# Schematics_PranavHackCard.net
KiCad netlist of a schematic drawn in EasyEDA
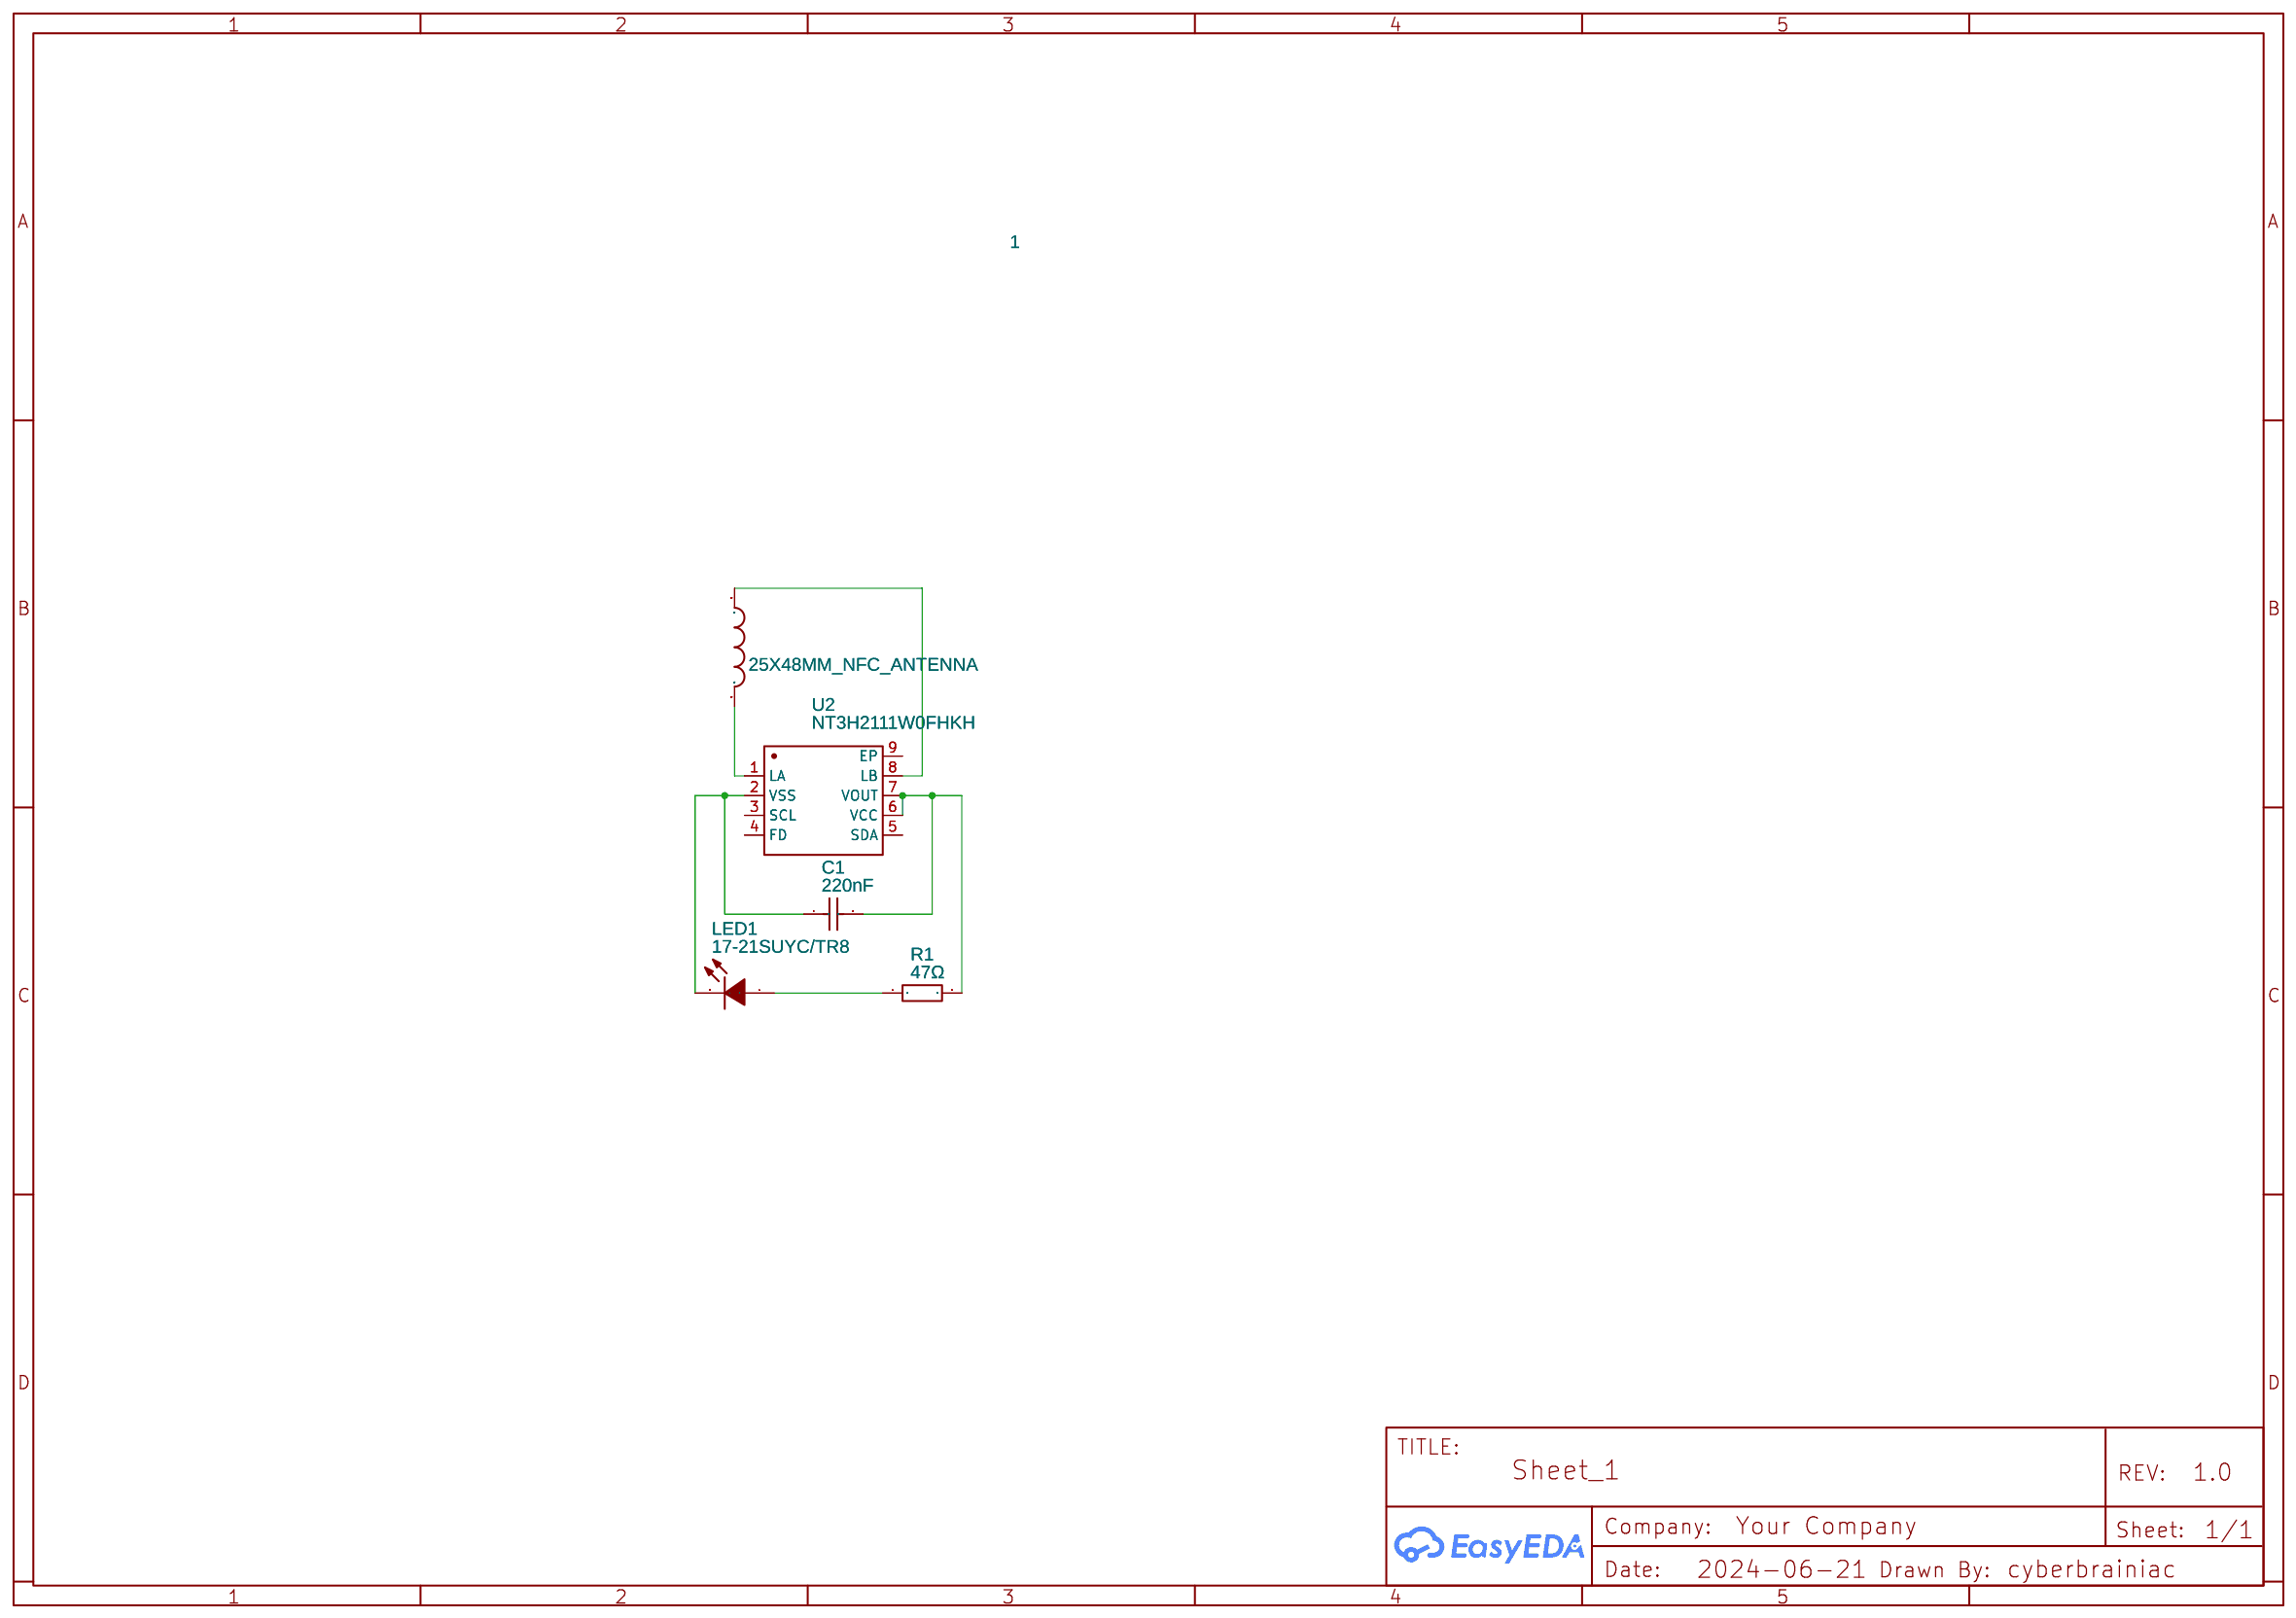
[diagram p0: schematic sheet]

(export (version "E")
  (design (tool "Eeschema 10.0.6"))
  (components
    (comp (ref "1") (value "25X48MM_NFC_ANTENNA") (libsource (lib "") (part "25X48MM_NFC_ANTENNA")))
    (comp (ref "C1")
      (value "220nF")
      (fields
        (field (name "Manufacturer Part") "CL10B224KA8NNNC")
        (field (name "Manufacturer") "SAMSUNG(三星)")
      )
      (libsource (lib "") (part "CL10B224KA8NNNC"))
    )
    (comp (ref "LED1")
      (value "17-21SUYC/TR8")
      (fields (field (name "Manufacturer Part") "KT-0805黄灯") (field (name "Manufacturer") "KENTO"))
      (libsource (lib "") (part "17-21SUYC/TR8"))
    )
    (comp (ref "R1")
      (value "47Ω")
      (fields
        (field (name "Manufacturer Part") "0603WAF470JT5E")
        (field (name "Manufacturer") "UNI-ROYAL(厚声)")
      )
      (libsource (lib "") (part "0603WAF470JT5E"))
    )
    (comp (ref "U2")
      (value "NT3H2111W0FHKH")
      (fields (field (name "Manufacturer") "NXP(恩智浦)"))
      (libsource (lib "") (part "NT3H2111W0FHKH"))
    )
  )
  (nets
    (net (code "1") (name "Net-(LED1-+)") (class "Default")
      (node (ref "LED1") (pin "1") (pinfunction "+_1") (pintype "unspecified"))
      (node (ref "R1") (pin "1") (pinfunction "1_1") (pintype "input"))
    )
    (net (code "2") (name "Net-(LED1--)") (class "Default")
      (node (ref "C1") (pin "1") (pinfunction "1_1") (pintype "input"))
      (node (ref "LED1") (pin "2") (pinfunction "-_2") (pintype "unspecified"))
      (node (ref "U2") (pin "2") (pinfunction "VSS_2") (pintype "unspecified"))
    )
    (net (code "3") (name "Net-(U2-LA)") (class "Default")
      (node (ref "1") (pin "P$2") (pinfunction "P$2_P$2") (pintype "bidirectional"))
      (node (ref "U2") (pin "1") (pinfunction "LA_1") (pintype "unspecified"))
    )
    (net (code "4") (name "Net-(U2-LB)") (class "Default")
      (node (ref "1") (pin "P$1") (pinfunction "P$1_P$1") (pintype "bidirectional"))
      (node (ref "U2") (pin "8") (pinfunction "LB_8") (pintype "unspecified"))
    )
    (net (code "5") (name "Net-(U2-VCC)") (class "Default")
      (node (ref "C1") (pin "2") (pinfunction "2_2") (pintype "input"))
      (node (ref "R1") (pin "2") (pinfunction "2_2") (pintype "input"))
      (node (ref "U2") (pin "6") (pinfunction "VCC_6") (pintype "unspecified"))
      (node (ref "U2") (pin "7") (pinfunction "VOUT_7") (pintype "unspecified"))
    )
    (net (code "6") (name "unconnected-(U2-EP-Pad9)") (class "Default")
      (node (ref "U2") (pin "9") (pinfunction "EP_9") (pintype "unspecified"))
    )
    (net (code "7") (name "unconnected-(U2-FD-Pad4)") (class "Default")
      (node (ref "U2") (pin "4") (pinfunction "FD_4") (pintype "unspecified"))
    )
    (net (code "8") (name "unconnected-(U2-SCL-Pad3)") (class "Default")
      (node (ref "U2") (pin "3") (pinfunction "SCL_3") (pintype "unspecified"))
    )
    (net (code "9") (name "unconnected-(U2-SDA-Pad5)") (class "Default")
      (node (ref "U2") (pin "5") (pinfunction "SDA_5") (pintype "unspecified"))
    )
  )
)
